# thermo_single.net
KiCad netlist of a schematic drawn in EAGLE
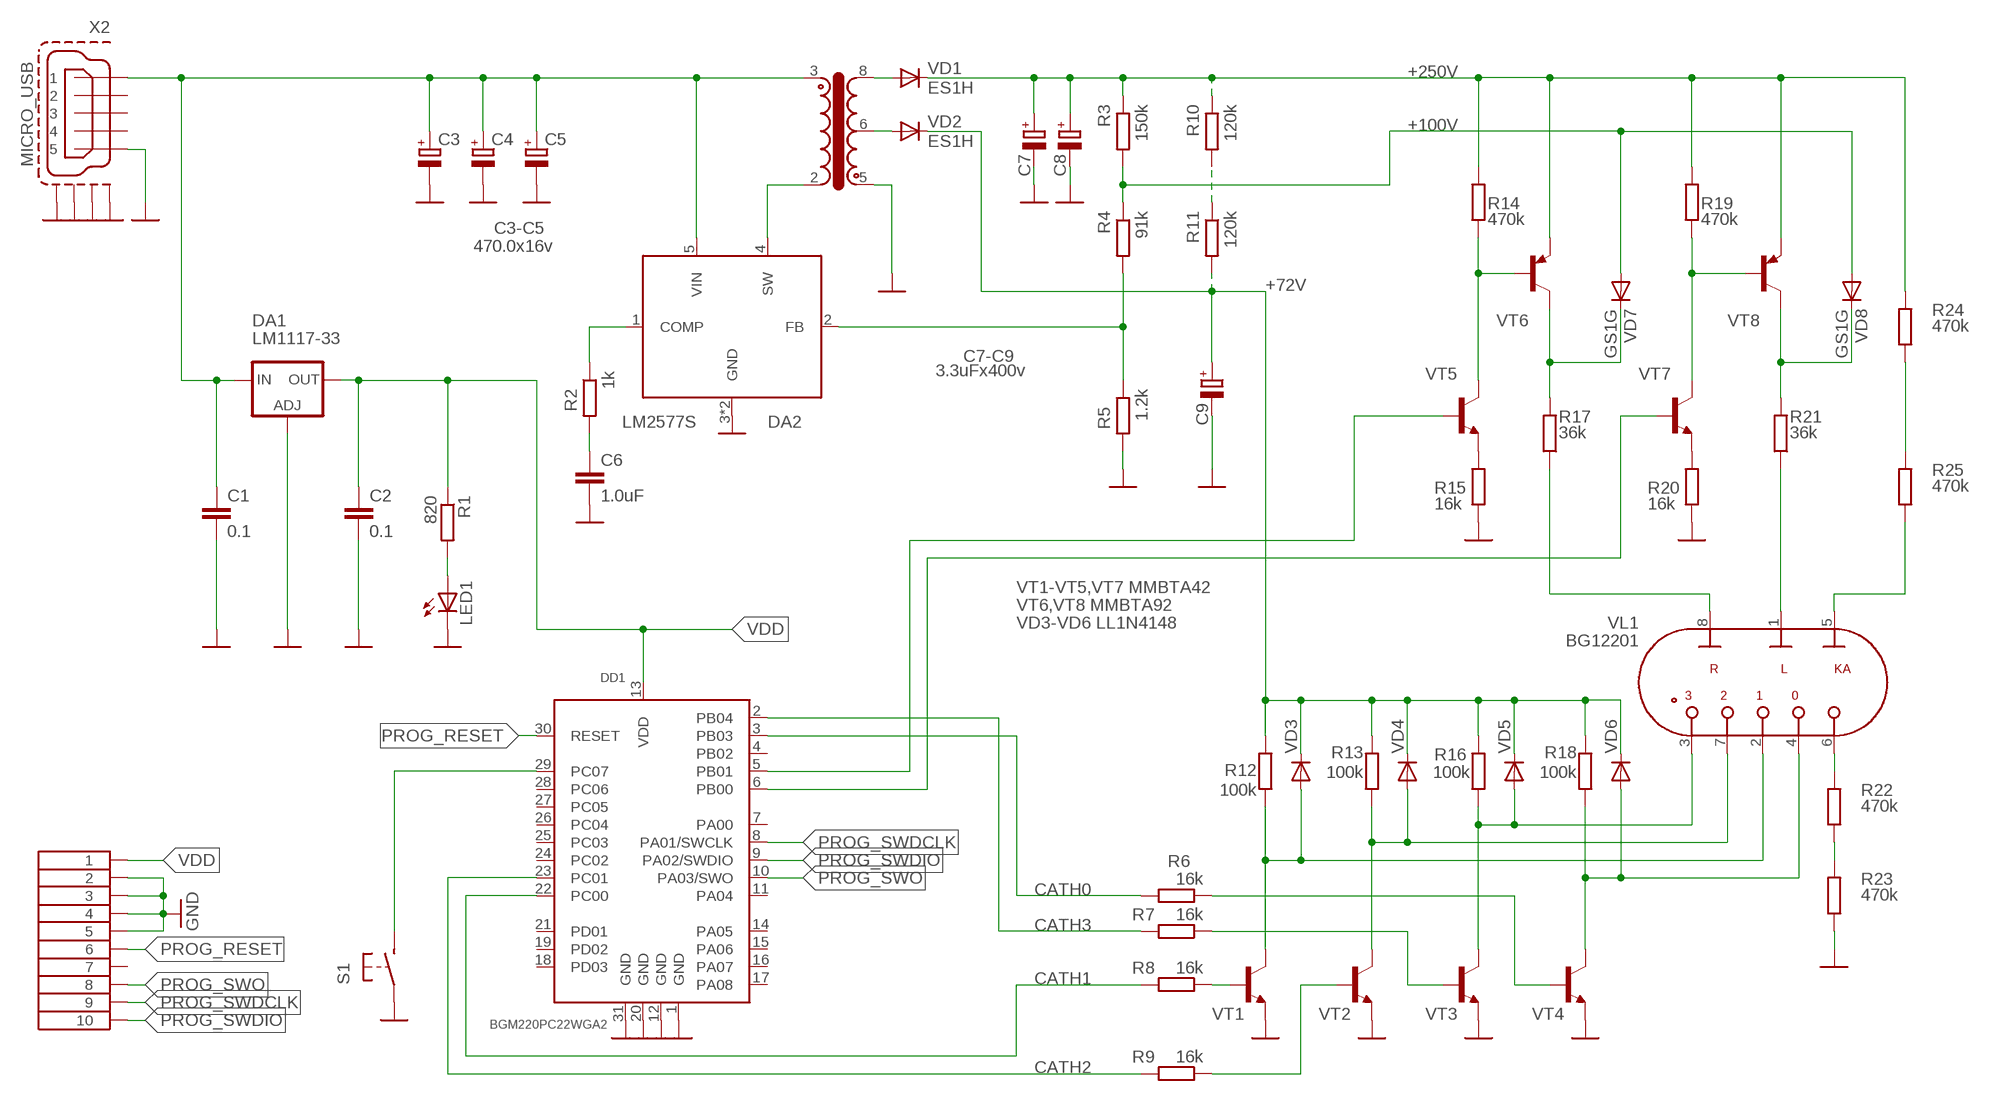
[diagram p0: schematic, sheet 1]

(export (version "E")
  (design (tool "Eeschema 10.0.6"))
  (components
    (comp (ref "C1")
      (value "0.1")
      (footprint "eagle-import:C0805")
      (libsource (lib "eagle-import") (part "C-EUC0805"))
    )
    (comp (ref "C2")
      (value "0.1")
      (footprint "eagle-import:C0805")
      (libsource (lib "eagle-import") (part "C-EUC0805"))
    )
    (comp (ref "C3")
      (value "470.0x16v")
      (footprint "eagle-import:PANASONIC_G")
      (libsource (lib "eagle-import") (part "CPOL-EUG"))
    )
    (comp (ref "C4")
      (value "470.0x16v")
      (footprint "eagle-import:PANASONIC_G")
      (libsource (lib "eagle-import") (part "CPOL-EUG"))
    )
    (comp (ref "C5")
      (value "470.0x16v")
      (footprint "eagle-import:PANASONIC_G")
      (libsource (lib "eagle-import") (part "CPOL-EUG"))
    )
    (comp (ref "C6")
      (value "1.0uF")
      (footprint "eagle-import:C1206")
      (libsource (lib "eagle-import") (part "C-EUC1206"))
    )
    (comp (ref "C7")
      (value "3.3uFx400v")
      (footprint "eagle-import:PANASONIC_G")
      (libsource (lib "eagle-import") (part "CPOL-EUG"))
    )
    (comp (ref "C8")
      (value "3.3uFx400v")
      (footprint "eagle-import:PANASONIC_G")
      (libsource (lib "eagle-import") (part "CPOL-EUG"))
    )
    (comp (ref "C9")
      (value "3.3uFx400v")
      (footprint "eagle-import:PANASONIC_G")
      (libsource (lib "eagle-import") (part "CPOL-EUG"))
    )
    (comp (ref "DA1")
      (value "LM1117-33")
      (footprint "eagle-import:SOT223")
      (libsource (lib "eagle-import") (part "LD117A?S33TR"))
    )
    (comp (ref "DA2")
      (value "LM2577S")
      (footprint "eagle-import:TO263-5")
      (libsource (lib "eagle-import") (part "LM2577S"))
    )
    (comp (ref "DD1")
      (value "BGM220PC22WGA2")
      (footprint "eagle-import:BGM13P22F512GEV2")
      (libsource (lib "eagle-import") (part "BGM220PC22WGA2"))
    )
    (comp (ref "LED1")
      (value "LEDP-LCC-2")
      (footprint "eagle-import:P-LCC-2")
      (libsource (lib "eagle-import") (part "LEDP-LCC-2"))
    )
    (comp (ref "R1")
      (value "820")
      (footprint "eagle-import:R0805")
      (libsource (lib "eagle-import") (part "R-EU_R0805"))
    )
    (comp (ref "R2")
      (value "1k")
      (footprint "eagle-import:R0805")
      (libsource (lib "eagle-import") (part "R-EU_R0805"))
    )
    (comp (ref "R3")
      (value "150k")
      (footprint "eagle-import:R0805")
      (libsource (lib "eagle-import") (part "R-EU_R0805"))
    )
    (comp (ref "R4")
      (value "91k")
      (footprint "eagle-import:R0805")
      (libsource (lib "eagle-import") (part "R-EU_R0805"))
    )
    (comp (ref "R5")
      (value "1.2k")
      (footprint "eagle-import:R0805")
      (libsource (lib "eagle-import") (part "R-EU_R0805"))
    )
    (comp (ref "R6")
      (value "16k")
      (footprint "eagle-import:R0805")
      (libsource (lib "eagle-import") (part "R-EU_R0805"))
    )
    (comp (ref "R7")
      (value "16k")
      (footprint "eagle-import:R0805")
      (libsource (lib "eagle-import") (part "R-EU_R0805"))
    )
    (comp (ref "R8")
      (value "16k")
      (footprint "eagle-import:R0805")
      (libsource (lib "eagle-import") (part "R-EU_R0805"))
    )
    (comp (ref "R9")
      (value "16k")
      (footprint "eagle-import:R0805")
      (libsource (lib "eagle-import") (part "R-EU_R0805"))
    )
    (comp (ref "R10")
      (value "120k")
      (footprint "eagle-import:R0805")
      (libsource (lib "eagle-import") (part "R-EU_R0805"))
    )
    (comp (ref "R11")
      (value "120k")
      (footprint "eagle-import:R0805")
      (libsource (lib "eagle-import") (part "R-EU_R0805"))
    )
    (comp (ref "R12")
      (value "100k")
      (footprint "eagle-import:R0805")
      (libsource (lib "eagle-import") (part "R-EU_R0805"))
    )
    (comp (ref "R13")
      (value "100k")
      (footprint "eagle-import:R0805")
      (libsource (lib "eagle-import") (part "R-EU_R0805"))
    )
    (comp (ref "R14")
      (value "470k")
      (footprint "eagle-import:R0805")
      (libsource (lib "eagle-import") (part "R-EU_R0805"))
    )
    (comp (ref "R15")
      (value "16k")
      (footprint "eagle-import:R0805")
      (libsource (lib "eagle-import") (part "R-EU_R0805"))
    )
    (comp (ref "R16")
      (value "100k")
      (footprint "eagle-import:R0805")
      (libsource (lib "eagle-import") (part "R-EU_R0805"))
    )
    (comp (ref "R17")
      (value "36k")
      (footprint "eagle-import:R0805")
      (libsource (lib "eagle-import") (part "R-EU_R0805"))
    )
    (comp (ref "R18")
      (value "100k")
      (footprint "eagle-import:R0805")
      (libsource (lib "eagle-import") (part "R-EU_R0805"))
    )
    (comp (ref "R19")
      (value "470k")
      (footprint "eagle-import:R0805")
      (libsource (lib "eagle-import") (part "R-EU_R0805"))
    )
    (comp (ref "R20")
      (value "16k")
      (footprint "eagle-import:R0805")
      (libsource (lib "eagle-import") (part "R-EU_R0805"))
    )
    (comp (ref "R21")
      (value "36k")
      (footprint "eagle-import:R0805")
      (libsource (lib "eagle-import") (part "R-EU_R0805"))
    )
    (comp (ref "R22")
      (value "470k")
      (footprint "eagle-import:R0805")
      (libsource (lib "eagle-import") (part "R-EU_R0805"))
    )
    (comp (ref "R23")
      (value "470k")
      (footprint "eagle-import:R0805")
      (libsource (lib "eagle-import") (part "R-EU_R0805"))
    )
    (comp (ref "R24")
      (value "470k")
      (footprint "eagle-import:R0805")
      (libsource (lib "eagle-import") (part "R-EU_R0805"))
    )
    (comp (ref "R25")
      (value "470k")
      (footprint "eagle-import:R0805")
      (libsource (lib "eagle-import") (part "R-EU_R0805"))
    )
    (comp (ref "S1")
      (value "10-XXPTS636SJ25")
      (footprint "eagle-import:PTS636SJ25")
      (libsource (lib "eagle-import") (part "10-XXPTS636SJ25"))
    )
    (comp (ref "T1")
      (value "TRANSFFB")
      (footprint "eagle-import:EFD20-8")
      (libsource (lib "eagle-import") (part "TRANSFFB"))
    )
    (comp (ref "VD1")
      (value "ES1H")
      (footprint "eagle-import:DO-214AC")
      (libsource (lib "eagle-import") (part "dp_devices_DIODE-DO-214AC"))
    )
    (comp (ref "VD2")
      (value "ES1H")
      (footprint "eagle-import:DO-214AC")
      (libsource (lib "eagle-import") (part "dp_devices_DIODE-DO-214AC"))
    )
    (comp (ref "VD3")
      (value "LL4148")
      (footprint "eagle-import:SOD80C")
      (libsource (lib "eagle-import") (part "DIODE-SOD80C"))
    )
    (comp (ref "VD4")
      (value "LL4148")
      (footprint "eagle-import:SOD80C")
      (libsource (lib "eagle-import") (part "DIODE-SOD80C"))
    )
    (comp (ref "VD5")
      (value "LL4148")
      (footprint "eagle-import:SOD80C")
      (libsource (lib "eagle-import") (part "DIODE-SOD80C"))
    )
    (comp (ref "VD6")
      (value "LL4148")
      (footprint "eagle-import:SOD80C")
      (libsource (lib "eagle-import") (part "DIODE-SOD80C"))
    )
    (comp (ref "VD7")
      (value "GS1G")
      (footprint "eagle-import:DO-214AC")
      (libsource (lib "eagle-import") (part "dp_devices_DIODE-DO-214AC"))
    )
    (comp (ref "VD8")
      (value "GS1G")
      (footprint "eagle-import:DO-214AC")
      (libsource (lib "eagle-import") (part "dp_devices_DIODE-DO-214AC"))
    )
    (comp (ref "VL1")
      (value "BG12201")
      (footprint "eagle-import:BG12201")
      (libsource (lib "eagle-import") (part "BG12201"))
    )
    (comp (ref "VT1")
      (value "mmbta42")
      (footprint "eagle-import:SOT23-BEC")
      (libsource (lib "eagle-import") (part "-NPN-SOT23-BECMMBTA42LT1"))
    )
    (comp (ref "VT2")
      (value "mmbta42")
      (footprint "eagle-import:SOT23-BEC")
      (libsource (lib "eagle-import") (part "-NPN-SOT23-BECMMBTA42LT1"))
    )
    (comp (ref "VT3")
      (value "mmbta42")
      (footprint "eagle-import:SOT23-BEC")
      (libsource (lib "eagle-import") (part "-NPN-SOT23-BECMMBTA42LT1"))
    )
    (comp (ref "VT4")
      (value "mmbta42")
      (footprint "eagle-import:SOT23-BEC")
      (libsource (lib "eagle-import") (part "-NPN-SOT23-BECMMBTA42LT1"))
    )
    (comp (ref "VT5")
      (value "mmbta42")
      (footprint "eagle-import:SOT23-BEC")
      (libsource (lib "eagle-import") (part "-NPN-SOT23-BECMMBTA42LT1"))
    )
    (comp (ref "VT6")
      (value "mmbta92")
      (footprint "eagle-import:SOT23-BEC")
      (libsource (lib "eagle-import") (part "-PNP-SOT23-BECMMBTA92LT1"))
    )
    (comp (ref "VT7")
      (value "mmbta42")
      (footprint "eagle-import:SOT23-BEC")
      (libsource (lib "eagle-import") (part "-NPN-SOT23-BECMMBTA42LT1"))
    )
    (comp (ref "VT8")
      (value "mmbta92")
      (footprint "eagle-import:SOT23-BEC")
      (libsource (lib "eagle-import") (part "-PNP-SOT23-BECMMBTA92LT1"))
    )
    (comp (ref "X1")
      (value "PINHEAD2X5")
      (footprint "eagle-import:DS1031-08-2_5P8BS-4-1")
      (libsource (lib "eagle-import") (part "PINHEAD2X5"))
    )
    (comp (ref "X2")
      (value "MICRO_USB")
      (footprint "eagle-import:MICRO_USB_MOLEX")
      (libsource (lib "eagle-import") (part "MICRO_USB"))
    )
  )
  (nets
    (net (code "1") (name "/+72V") (class "Default")
      (node (ref "C9") (pin "+") (pinfunction "+_+") (pintype "passive"))
      (node (ref "R11") (pin "2") (pinfunction "2_2") (pintype "passive"))
      (node (ref "R12") (pin "2") (pinfunction "2_2") (pintype "passive"))
      (node (ref "R13") (pin "2") (pinfunction "2_2") (pintype "passive"))
      (node (ref "R16") (pin "2") (pinfunction "2_2") (pintype "passive"))
      (node (ref "R18") (pin "2") (pinfunction "2_2") (pintype "passive"))
      (node (ref "VD2") (pin "1") (pinfunction "C_1") (pintype "passive"))
      (node (ref "VD3") (pin "C") (pinfunction "C_C") (pintype "passive"))
      (node (ref "VD4") (pin "C") (pinfunction "C_C") (pintype "passive"))
      (node (ref "VD5") (pin "C") (pinfunction "C_C") (pintype "passive"))
      (node (ref "VD6") (pin "C") (pinfunction "C_C") (pintype "passive"))
    )
    (net (code "2") (name "/+100V") (class "Default")
      (node (ref "R3") (pin "2") (pinfunction "2_2") (pintype "passive"))
      (node (ref "R4") (pin "1") (pinfunction "1_1") (pintype "passive"))
      (node (ref "VD7") (pin "2") (pinfunction "A_2") (pintype "passive"))
      (node (ref "VD8") (pin "2") (pinfunction "A_2") (pintype "passive"))
    )
    (net (code "3") (name "/+250V") (class "Default")
      (node (ref "C7") (pin "+") (pinfunction "+_+") (pintype "passive"))
      (node (ref "C8") (pin "+") (pinfunction "+_+") (pintype "passive"))
      (node (ref "R10") (pin "1") (pinfunction "1_1") (pintype "passive"))
      (node (ref "R14") (pin "2") (pinfunction "2_2") (pintype "passive"))
      (node (ref "R19") (pin "2") (pinfunction "2_2") (pintype "passive"))
      (node (ref "R24") (pin "2") (pinfunction "2_2") (pintype "passive"))
      (node (ref "R3") (pin "1") (pinfunction "1_1") (pintype "passive"))
      (node (ref "VD1") (pin "1") (pinfunction "C_1") (pintype "passive"))
      (node (ref "VT6") (pin "E") (pinfunction "E_E") (pintype "passive"))
      (node (ref "VT8") (pin "E") (pinfunction "E_E") (pintype "passive"))
    )
    (net (code "4") (name "/CATH0") (class "Default")
      (node (ref "DD1") (pin "3") (pinfunction "PB03_3") (pintype "bidirectional"))
      (node (ref "R6") (pin "2") (pinfunction "2_2") (pintype "passive"))
    )
    (net (code "5") (name "/CATH1") (class "Default")
      (node (ref "DD1") (pin "22") (pinfunction "PC00_22") (pintype "bidirectional"))
      (node (ref "R8") (pin "2") (pinfunction "2_2") (pintype "passive"))
    )
    (net (code "6") (name "/CATH2") (class "Default")
      (node (ref "DD1") (pin "23") (pinfunction "PC01_23") (pintype "bidirectional"))
      (node (ref "R9") (pin "2") (pinfunction "2_2") (pintype "passive"))
    )
    (net (code "7") (name "/CATH3") (class "Default")
      (node (ref "DD1") (pin "2") (pinfunction "PB04_2") (pintype "bidirectional"))
      (node (ref "R7") (pin "2") (pinfunction "2_2") (pintype "passive"))
    )
    (net (code "8") (name "GND") (class "Default")
      (node (ref "C1") (pin "2") (pinfunction "2_2") (pintype "passive"))
      (node (ref "C2") (pin "2") (pinfunction "2_2") (pintype "passive"))
      (node (ref "C3") (pin "-") (pinfunction "-_-") (pintype "passive"))
      (node (ref "C4") (pin "-") (pinfunction "-_-") (pintype "passive"))
      (node (ref "C5") (pin "-") (pinfunction "-_-") (pintype "passive"))
      (node (ref "C6") (pin "2") (pinfunction "2_2") (pintype "passive"))
      (node (ref "C7") (pin "-") (pinfunction "-_-") (pintype "passive"))
      (node (ref "C8") (pin "-") (pinfunction "-_-") (pintype "passive"))
      (node (ref "C9") (pin "-") (pinfunction "-_-") (pintype "passive"))
      (node (ref "DA1") (pin "1") (pinfunction "ADJ_1") (pintype "input"))
      (node (ref "DA2") (pin "3") (pinfunction "GND_3") (pintype "bidirectional"))
      (node (ref "DA2") (pin "6") (pinfunction "GND_6") (pintype "bidirectional"))
      (node (ref "DD1") (pin "1") (pinfunction "GND_1") (pintype "power_in"))
      (node (ref "DD1") (pin "12") (pinfunction "GND_12") (pintype "power_in"))
      (node (ref "DD1") (pin "20") (pinfunction "GND_20") (pintype "power_in"))
      (node (ref "DD1") (pin "31") (pinfunction "GND_31") (pintype "power_in"))
      (node (ref "LED1") (pin "C") (pinfunction "C_C") (pintype "passive"))
      (node (ref "R15") (pin "1") (pinfunction "1_1") (pintype "passive"))
      (node (ref "R20") (pin "1") (pinfunction "1_1") (pintype "passive"))
      (node (ref "R23") (pin "1") (pinfunction "1_1") (pintype "passive"))
      (node (ref "R5") (pin "2") (pinfunction "2_2") (pintype "passive"))
      (node (ref "S1") (pin "P$1") (pinfunction "P_P$1") (pintype "passive"))
      (node (ref "T1") (pin "5") (pinfunction "P$4_5") (pintype "bidirectional"))
      (node (ref "VT1") (pin "E") (pinfunction "E_E") (pintype "passive"))
      (node (ref "VT2") (pin "E") (pinfunction "E_E") (pintype "passive"))
      (node (ref "VT3") (pin "E") (pinfunction "E_E") (pintype "passive"))
      (node (ref "VT4") (pin "E") (pinfunction "E_E") (pintype "passive"))
      (node (ref "X1") (pin "2") (pinfunction "2_2") (pintype "bidirectional"))
      (node (ref "X1") (pin "3") (pinfunction "3_3") (pintype "bidirectional"))
      (node (ref "X1") (pin "4") (pinfunction "4_4") (pintype "bidirectional"))
      (node (ref "X1") (pin "5") (pinfunction "5_5") (pintype "bidirectional"))
      (node (ref "X2") (pin "5") (pinfunction "5_5") (pintype "input"))
      (node (ref "X2") (pin "P$1") (pinfunction "S1_P$1") (pintype "passive"))
      (node (ref "X2") (pin "P$2") (pinfunction "S2_P$2") (pintype "passive"))
      (node (ref "X2") (pin "P$4") (pinfunction "S3_P$4") (pintype "passive"))
      (node (ref "X2") (pin "P$5") (pinfunction "S4_P$5") (pintype "passive"))
    )
    (net (code "9") (name "Net-(C6-Pad1)") (class "Default")
      (node (ref "C6") (pin "1") (pinfunction "1_1") (pintype "passive"))
      (node (ref "R2") (pin "2") (pinfunction "2_2") (pintype "passive"))
    )
    (net (code "10") (name "Net-(DA1-IN)") (class "Default")
      (node (ref "C1") (pin "1") (pinfunction "1_1") (pintype "passive"))
      (node (ref "C3") (pin "+") (pinfunction "+_+") (pintype "passive"))
      (node (ref "C4") (pin "+") (pinfunction "+_+") (pintype "passive"))
      (node (ref "C5") (pin "+") (pinfunction "+_+") (pintype "passive"))
      (node (ref "DA1") (pin "3") (pinfunction "IN_3") (pintype "input"))
      (node (ref "DA2") (pin "5") (pinfunction "VIN_5") (pintype "bidirectional"))
      (node (ref "T1") (pin "3") (pinfunction "P$2_3") (pintype "bidirectional"))
      (node (ref "X2") (pin "1") (pinfunction "1_1") (pintype "input"))
    )
    (net (code "11") (name "Net-(DA2-COMP)") (class "Default")
      (node (ref "DA2") (pin "1") (pinfunction "COMP_1") (pintype "bidirectional"))
      (node (ref "R2") (pin "1") (pinfunction "1_1") (pintype "passive"))
    )
    (net (code "12") (name "Net-(DA2-FB)") (class "Default")
      (node (ref "DA2") (pin "2") (pinfunction "FB_2") (pintype "bidirectional"))
      (node (ref "R4") (pin "2") (pinfunction "2_2") (pintype "passive"))
      (node (ref "R5") (pin "1") (pinfunction "1_1") (pintype "passive"))
    )
    (net (code "13") (name "Net-(DA2-SW)") (class "Default")
      (node (ref "DA2") (pin "4") (pinfunction "SW_4") (pintype "bidirectional"))
      (node (ref "T1") (pin "2") (pinfunction "P$1_2") (pintype "bidirectional"))
    )
    (net (code "14") (name "Net-(DD1-PB00)") (class "Default")
      (node (ref "DD1") (pin "6") (pinfunction "PB00_6") (pintype "bidirectional"))
      (node (ref "VT7") (pin "B") (pinfunction "B_B") (pintype "passive"))
    )
    (net (code "15") (name "Net-(DD1-PB01)") (class "Default")
      (node (ref "DD1") (pin "5") (pinfunction "PB01_5") (pintype "bidirectional"))
      (node (ref "VT5") (pin "B") (pinfunction "B_B") (pintype "passive"))
    )
    (net (code "16") (name "Net-(DD1-PC07)") (class "Default")
      (node (ref "DD1") (pin "29") (pinfunction "PC07_29") (pintype "bidirectional"))
      (node (ref "S1") (pin "P$2") (pinfunction "S_P$2") (pintype "passive"))
    )
    (net (code "17") (name "Net-(LED1-PadA)") (class "Default")
      (node (ref "LED1") (pin "A") (pinfunction "A_A") (pintype "passive"))
      (node (ref "R1") (pin "2") (pinfunction "2_2") (pintype "passive"))
    )
    (net (code "18") (name "Net-(R6-Pad1)") (class "Default")
      (node (ref "R6") (pin "1") (pinfunction "1_1") (pintype "passive"))
      (node (ref "VT4") (pin "B") (pinfunction "B_B") (pintype "passive"))
    )
    (net (code "19") (name "Net-(R7-Pad1)") (class "Default")
      (node (ref "R7") (pin "1") (pinfunction "1_1") (pintype "passive"))
      (node (ref "VT3") (pin "B") (pinfunction "B_B") (pintype "passive"))
    )
    (net (code "20") (name "Net-(R8-Pad1)") (class "Default")
      (node (ref "R8") (pin "1") (pinfunction "1_1") (pintype "passive"))
      (node (ref "VT1") (pin "B") (pinfunction "B_B") (pintype "passive"))
    )
    (net (code "21") (name "Net-(R9-Pad1)") (class "Default")
      (node (ref "R9") (pin "1") (pinfunction "1_1") (pintype "passive"))
      (node (ref "VT2") (pin "B") (pinfunction "B_B") (pintype "passive"))
    )
    (net (code "22") (name "Net-(R10-Pad2)") (class "Default")
      (node (ref "R10") (pin "2") (pinfunction "2_2") (pintype "passive"))
      (node (ref "R11") (pin "1") (pinfunction "1_1") (pintype "passive"))
    )
    (net (code "23") (name "Net-(R14-Pad1)") (class "Default")
      (node (ref "R14") (pin "1") (pinfunction "1_1") (pintype "passive"))
      (node (ref "VT5") (pin "C") (pinfunction "C_C") (pintype "passive"))
      (node (ref "VT6") (pin "B") (pinfunction "B_B") (pintype "passive"))
    )
    (net (code "24") (name "Net-(R15-Pad2)") (class "Default")
      (node (ref "R15") (pin "2") (pinfunction "2_2") (pintype "passive"))
      (node (ref "VT5") (pin "E") (pinfunction "E_E") (pintype "passive"))
    )
    (net (code "25") (name "Net-(R19-Pad1)") (class "Default")
      (node (ref "R19") (pin "1") (pinfunction "1_1") (pintype "passive"))
      (node (ref "VT7") (pin "C") (pinfunction "C_C") (pintype "passive"))
      (node (ref "VT8") (pin "B") (pinfunction "B_B") (pintype "passive"))
    )
    (net (code "26") (name "Net-(R20-Pad2)") (class "Default")
      (node (ref "R20") (pin "2") (pinfunction "2_2") (pintype "passive"))
      (node (ref "VT7") (pin "E") (pinfunction "E_E") (pintype "passive"))
    )
    (net (code "27") (name "Net-(R22-Pad1)") (class "Default")
      (node (ref "R22") (pin "1") (pinfunction "1_1") (pintype "passive"))
      (node (ref "R23") (pin "2") (pinfunction "2_2") (pintype "passive"))
    )
    (net (code "28") (name "Net-(R24-Pad1)") (class "Default")
      (node (ref "R24") (pin "1") (pinfunction "1_1") (pintype "passive"))
      (node (ref "R25") (pin "2") (pinfunction "2_2") (pintype "passive"))
    )
    (net (code "29") (name "Net-(T1-P$3)") (class "Default")
      (node (ref "T1") (pin "8") (pinfunction "P$3_8") (pintype "bidirectional"))
      (node (ref "VD1") (pin "2") (pinfunction "A_2") (pintype "passive"))
    )
    (net (code "30") (name "Net-(T1-P$5)") (class "Default")
      (node (ref "T1") (pin "6") (pinfunction "P$5_6") (pintype "bidirectional"))
      (node (ref "VD2") (pin "2") (pinfunction "A_2") (pintype "passive"))
    )
    (net (code "31") (name "Net-(VD7-C)") (class "Default")
      (node (ref "R17") (pin "2") (pinfunction "2_2") (pintype "passive"))
      (node (ref "VD7") (pin "1") (pinfunction "C_1") (pintype "passive"))
      (node (ref "VT6") (pin "C") (pinfunction "C_C") (pintype "passive"))
    )
    (net (code "32") (name "Net-(VD8-C)") (class "Default")
      (node (ref "R21") (pin "2") (pinfunction "2_2") (pintype "passive"))
      (node (ref "VD8") (pin "1") (pinfunction "C_1") (pintype "passive"))
      (node (ref "VT8") (pin "C") (pinfunction "C_C") (pintype "passive"))
    )
    (net (code "33") (name "Net-(VL1-C1)") (class "Default")
      (node (ref "R12") (pin "1") (pinfunction "1_1") (pintype "passive"))
      (node (ref "VD3") (pin "A") (pinfunction "A_A") (pintype "passive"))
      (node (ref "VL1") (pin "2") (pinfunction "C1_2") (pintype "bidirectional"))
      (node (ref "VT1") (pin "C") (pinfunction "C_C") (pintype "passive"))
    )
    (net (code "34") (name "Net-(VL1-C2)") (class "Default")
      (node (ref "R13") (pin "1") (pinfunction "1_1") (pintype "passive"))
      (node (ref "VD4") (pin "A") (pinfunction "A_A") (pintype "passive"))
      (node (ref "VL1") (pin "7") (pinfunction "C2_7") (pintype "bidirectional"))
      (node (ref "VT2") (pin "C") (pinfunction "C_C") (pintype "passive"))
    )
    (net (code "35") (name "Net-(VL1-C3)") (class "Default")
      (node (ref "R16") (pin "1") (pinfunction "1_1") (pintype "passive"))
      (node (ref "VD5") (pin "A") (pinfunction "A_A") (pintype "passive"))
      (node (ref "VL1") (pin "3") (pinfunction "C3_3") (pintype "bidirectional"))
      (node (ref "VT3") (pin "C") (pinfunction "C_C") (pintype "passive"))
    )
    (net (code "36") (name "Net-(VL1-CR)") (class "Default")
      (node (ref "R18") (pin "1") (pinfunction "1_1") (pintype "passive"))
      (node (ref "VD6") (pin "A") (pinfunction "A_A") (pintype "passive"))
      (node (ref "VL1") (pin "4") (pinfunction "CR_4") (pintype "bidirectional"))
      (node (ref "VT4") (pin "C") (pinfunction "C_C") (pintype "passive"))
    )
    (net (code "37") (name "Net-(VL1-KA_A)") (class "Default")
      (node (ref "R25") (pin "1") (pinfunction "1_1") (pintype "passive"))
      (node (ref "VL1") (pin "5") (pinfunction "KA_A_5") (pintype "bidirectional"))
    )
    (net (code "38") (name "Net-(VL1-KA_C)") (class "Default")
      (node (ref "R22") (pin "2") (pinfunction "2_2") (pintype "passive"))
      (node (ref "VL1") (pin "6") (pinfunction "KA_C_6") (pintype "bidirectional"))
    )
    (net (code "39") (name "Net-(VL1-LA)") (class "Default")
      (node (ref "R21") (pin "1") (pinfunction "1_1") (pintype "passive"))
      (node (ref "VL1") (pin "1") (pinfunction "LA_1") (pintype "bidirectional"))
    )
    (net (code "40") (name "Net-(VL1-RA)") (class "Default")
      (node (ref "R17") (pin "1") (pinfunction "1_1") (pintype "passive"))
      (node (ref "VL1") (pin "8") (pinfunction "RA_8") (pintype "bidirectional"))
    )
    (net (code "41") (name "PROG_RESET") (class "Default")
      (node (ref "DD1") (pin "30") (pinfunction "RESET_30") (pintype "bidirectional"))
      (node (ref "X1") (pin "6") (pinfunction "6_6") (pintype "bidirectional"))
    )
    (net (code "42") (name "PROG_SWDCLK") (class "Default")
      (node (ref "DD1") (pin "8") (pinfunction "PA01/SWCLK_8") (pintype "bidirectional"))
      (node (ref "X1") (pin "9") (pinfunction "9_9") (pintype "bidirectional"))
    )
    (net (code "43") (name "PROG_SWDIO") (class "Default")
      (node (ref "DD1") (pin "9") (pinfunction "PA02/SWDIO_9") (pintype "bidirectional"))
      (node (ref "X1") (pin "10") (pinfunction "10_10") (pintype "bidirectional"))
    )
    (net (code "44") (name "PROG_SWO") (class "Default")
      (node (ref "DD1") (pin "10") (pinfunction "PA03/SWO_10") (pintype "bidirectional"))
      (node (ref "X1") (pin "8") (pinfunction "8_8") (pintype "bidirectional"))
    )
    (net (code "45") (name "VDD") (class "Default")
      (node (ref "C2") (pin "1") (pinfunction "1_1") (pintype "passive"))
      (node (ref "DA1") (pin "4") (pinfunction "OUT_4") (pintype "passive"))
      (node (ref "DD1") (pin "13") (pinfunction "VDD_13") (pintype "power_in"))
      (node (ref "R1") (pin "1") (pinfunction "1_1") (pintype "passive"))
      (node (ref "X1") (pin "1") (pinfunction "1_1") (pintype "bidirectional"))
    )
    (net (code "46") (name "unconnected-(DD1-PA00-Pad7)") (class "Default")
      (node (ref "DD1") (pin "7") (pinfunction "PA00_7") (pintype "bidirectional"))
    )
    (net (code "47") (name "unconnected-(DD1-PA04-Pad11)") (class "Default")
      (node (ref "DD1") (pin "11") (pinfunction "PA04_11") (pintype "bidirectional"))
    )
    (net (code "48") (name "unconnected-(DD1-PA05-Pad14)") (class "Default")
      (node (ref "DD1") (pin "14") (pinfunction "PA05_14") (pintype "bidirectional"))
    )
    (net (code "49") (name "unconnected-(DD1-PA06-Pad15)") (class "Default")
      (node (ref "DD1") (pin "15") (pinfunction "PA06_15") (pintype "bidirectional"))
    )
    (net (code "50") (name "unconnected-(DD1-PA07-Pad16)") (class "Default")
      (node (ref "DD1") (pin "16") (pinfunction "PA07_16") (pintype "bidirectional"))
    )
    (net (code "51") (name "unconnected-(DD1-PA08-Pad17)") (class "Default")
      (node (ref "DD1") (pin "17") (pinfunction "PA08_17") (pintype "bidirectional"))
    )
    (net (code "52") (name "unconnected-(DD1-PB02-Pad4)") (class "Default")
      (node (ref "DD1") (pin "4") (pinfunction "PB02_4") (pintype "bidirectional"))
    )
    (net (code "53") (name "unconnected-(DD1-PC02-Pad24)") (class "Default")
      (node (ref "DD1") (pin "24") (pinfunction "PC02_24") (pintype "bidirectional"))
    )
    (net (code "54") (name "unconnected-(DD1-PC03-Pad25)") (class "Default")
      (node (ref "DD1") (pin "25") (pinfunction "PC03_25") (pintype "bidirectional"))
    )
    (net (code "55") (name "unconnected-(DD1-PC04-Pad26)") (class "Default")
      (node (ref "DD1") (pin "26") (pinfunction "PC04_26") (pintype "bidirectional"))
    )
    (net (code "56") (name "unconnected-(DD1-PC05-Pad27)") (class "Default")
      (node (ref "DD1") (pin "27") (pinfunction "PC05_27") (pintype "bidirectional"))
    )
    (net (code "57") (name "unconnected-(DD1-PC06-Pad28)") (class "Default")
      (node (ref "DD1") (pin "28") (pinfunction "PC06_28") (pintype "bidirectional"))
    )
    (net (code "58") (name "unconnected-(DD1-PD01-Pad21)") (class "Default")
      (node (ref "DD1") (pin "21") (pinfunction "PD01_21") (pintype "bidirectional"))
    )
    (net (code "59") (name "unconnected-(DD1-PD02-Pad19)") (class "Default")
      (node (ref "DD1") (pin "19") (pinfunction "PD02_19") (pintype "bidirectional"))
    )
    (net (code "60") (name "unconnected-(DD1-PD03-Pad18)") (class "Default")
      (node (ref "DD1") (pin "18") (pinfunction "PD03_18") (pintype "bidirectional"))
    )
    (net (code "61") (name "unconnected-(X1-Pad7)") (class "Default")
      (node (ref "X1") (pin "7") (pinfunction "7_7") (pintype "bidirectional"))
    )
    (net (code "62") (name "unconnected-(X2-Pad2)") (class "Default")
      (node (ref "X2") (pin "2") (pinfunction "2_2") (pintype "input"))
    )
    (net (code "63") (name "unconnected-(X2-Pad3)") (class "Default")
      (node (ref "X2") (pin "3") (pinfunction "3_3") (pintype "input"))
    )
    (net (code "64") (name "unconnected-(X2-Pad4)") (class "Default")
      (node (ref "X2") (pin "4") (pinfunction "4_4") (pintype "input"))
    )
  )
)
